# design.net
KiCad netlist of a schematic drawn in Altium Designer
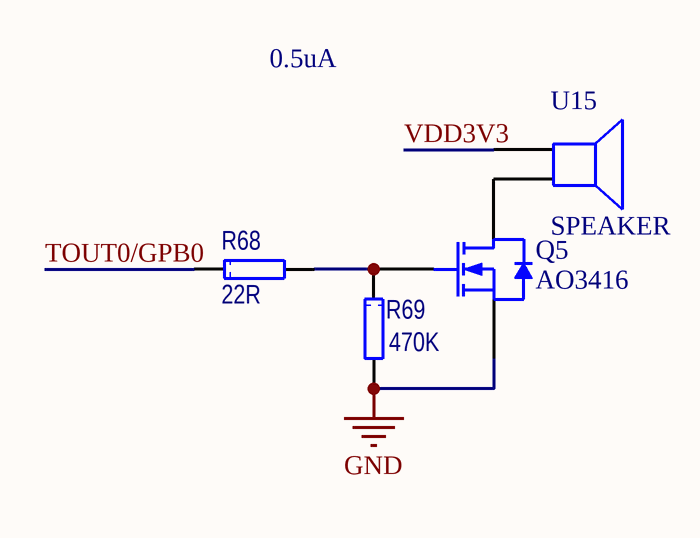
[diagram p0: 蜂鸣器.SchDoc]

(export (version "E")
  (design (tool "Eeschema 10.0.6"))
  (components
    (comp (ref "Q5")
      (value "AO3416")
      (footprint "SOT23_N")
      (description "NMOS")
      (fields (field (name "PUBLISHER") "Altium Limited"))
      (libsource (lib "Philips Discrete MOSFET - Low Power") (part "2N7002"))
    )
    (comp (ref "R68")
      (value "22R")
      (footprint "1608[0603]R")
      (description "RES")
      (fields (field (name "MANUFACTURER") "vishay"))
      (libsource (lib "*") (part "RES"))
    )
    (comp (ref "R69")
      (value "470K")
      (footprint "1608[0603]R")
      (description "RES")
      (fields (field (name "MANUFACTURER") "vishay"))
      (libsource (lib "*") (part "RES"))
    )
    (comp (ref "U15")
      (value "SPEAKER")
      (footprint "Speaker")
      (description "BUZ")
      (libsource (lib "*") (part "SPEAKER"))
    )
  )
  (nets
    (net (code "1") (name "/TOUT0{slash}GPB0") (class "Default")
      (node (ref "R68") (pin "1") (pinfunction "1_1") (pintype "passive"))
    )
    (net (code "2") (name "/VDD3V3") (class "Default")
      (node (ref "U15") (pin "1") (pinfunction "1_1") (pintype "passive"))
    )
    (net (code "3") (name "GND") (class "Default")
      (node (ref "Q5") (pin "2") (pinfunction "S_2") (pintype "passive"))
      (node (ref "R69") (pin "2") (pinfunction "2_2") (pintype "passive"))
    )
    (net (code "4") (name "Net-(Q5-D)") (class "Default")
      (node (ref "Q5") (pin "3") (pinfunction "D_3") (pintype "passive"))
      (node (ref "U15") (pin "2") (pinfunction "2_2") (pintype "passive"))
    )
    (net (code "5") (name "Net-(Q5-G)") (class "Default")
      (node (ref "Q5") (pin "1") (pinfunction "G_1") (pintype "passive"))
      (node (ref "R68") (pin "2") (pinfunction "2_2") (pintype "passive"))
      (node (ref "R69") (pin "1") (pinfunction "1_1") (pintype "passive"))
    )
  )
)
